# PCB_V1_7_1.net
KiCad netlist of a schematic drawn in EAGLE
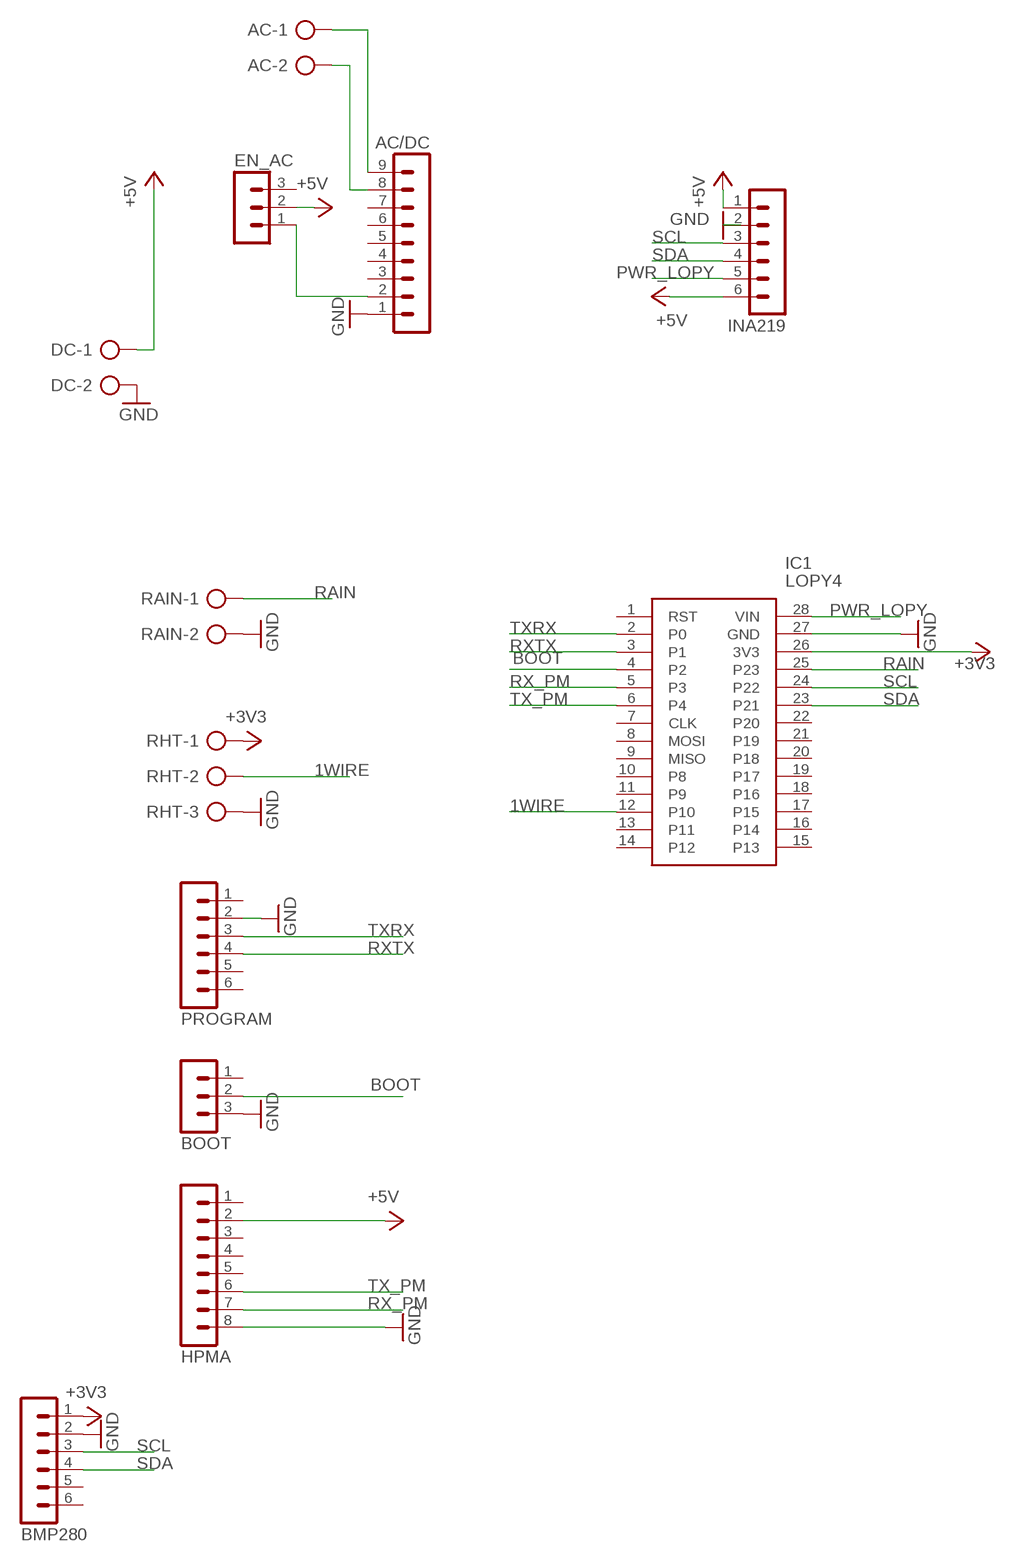
[diagram p0: schematic, sheet 1]

(export (version "E")
  (design (tool "Eeschema 10.0.6"))
  (components
    (comp (ref "AC")
      (value "AK300/2")
      (footprint "eagle-import:AK300_2")
      (libsource (lib "eagle-import") (part "AK300/2"))
    )
    (comp (ref "AC/DC")
      (value "MA09-1")
      (footprint "eagle-import:MA09-1")
      (libsource (lib "eagle-import") (part "MA09-1"))
    )
    (comp (ref "BMP280")
      (value "MA06-1")
      (footprint "eagle-import:MA06-1")
      (libsource (lib "eagle-import") (part "MA06-1"))
    )
    (comp (ref "BOOT")
      (value "MA03-1")
      (footprint "eagle-import:MA03-1")
      (libsource (lib "eagle-import") (part "MA03-1"))
    )
    (comp (ref "DC")
      (value "AK300/2")
      (footprint "eagle-import:AK300_2")
      (libsource (lib "eagle-import") (part "AK300/2"))
    )
    (comp (ref "EN_AC")
      (value "MA03-1")
      (footprint "eagle-import:MA03-1")
      (libsource (lib "eagle-import") (part "MA03-1"))
    )
    (comp (ref "HPMA")
      (value "MA08-1")
      (footprint "eagle-import:MA08-1")
      (libsource (lib "eagle-import") (part "MA08-1"))
    )
    (comp (ref "IC1")
      (value "LOPY4")
      (footprint "eagle-import:LOPY4")
      (fields (field (name "MOUSER_PART_NUMBER") "365-LOPY4"))
      (libsource (lib "eagle-import") (part "LOPY4"))
    )
    (comp (ref "INA219")
      (value "MA06-1")
      (footprint "eagle-import:MA06-1")
      (libsource (lib "eagle-import") (part "MA06-1"))
    )
    (comp (ref "PROGRAM")
      (value "MA06-1")
      (footprint "eagle-import:MA06-1")
      (libsource (lib "eagle-import") (part "MA06-1"))
    )
    (comp (ref "RAIN")
      (value "AK300/2")
      (footprint "eagle-import:AK300_2")
      (libsource (lib "eagle-import") (part "AK300/2"))
    )
    (comp (ref "RHT")
      (value "AK300/3")
      (footprint "eagle-import:AK300_3")
      (libsource (lib "eagle-import") (part "AK300/3"))
    )
  )
  (nets
    (net (code "1") (name "+3V3") (class "Default")
      (node (ref "BMP280") (pin "1") (pinfunction "1_1") (pintype "passive"))
      (node (ref "IC1") (pin "26") (pinfunction "3V3_26") (pintype "bidirectional"))
      (node (ref "RHT") (pin "1") (pinfunction "KL_1") (pintype "passive"))
    )
    (net (code "2") (name "+5V") (class "Default")
      (node (ref "DC") (pin "1") (pinfunction "KL_1") (pintype "passive"))
      (node (ref "EN_AC") (pin "2") (pinfunction "2_2") (pintype "passive"))
      (node (ref "HPMA") (pin "2") (pinfunction "2_2") (pintype "passive"))
      (node (ref "INA219") (pin "1") (pinfunction "1_1") (pintype "passive"))
      (node (ref "INA219") (pin "6") (pinfunction "6_6") (pintype "passive"))
    )
    (net (code "3") (name "/1WIRE") (class "Default")
      (node (ref "IC1") (pin "12") (pinfunction "P10_12") (pintype "bidirectional"))
      (node (ref "RHT") (pin "2") (pinfunction "KL_2") (pintype "passive"))
    )
    (net (code "4") (name "/BOOT") (class "Default")
      (node (ref "BOOT") (pin "2") (pinfunction "2_2") (pintype "passive"))
      (node (ref "IC1") (pin "4") (pinfunction "P2_4") (pintype "bidirectional"))
    )
    (net (code "5") (name "/PWR_LOPY") (class "Default")
      (node (ref "IC1") (pin "28") (pinfunction "VIN_28") (pintype "bidirectional"))
      (node (ref "INA219") (pin "5") (pinfunction "5_5") (pintype "passive"))
    )
    (net (code "6") (name "/RAIN") (class "Default")
      (node (ref "IC1") (pin "25") (pinfunction "P23_25") (pintype "bidirectional"))
      (node (ref "RAIN") (pin "1") (pinfunction "KL_1") (pintype "passive"))
    )
    (net (code "7") (name "/RXTX") (class "Default")
      (node (ref "IC1") (pin "3") (pinfunction "P1_3") (pintype "bidirectional"))
      (node (ref "PROGRAM") (pin "4") (pinfunction "4_4") (pintype "passive"))
    )
    (net (code "8") (name "/RX_PM") (class "Default")
      (node (ref "HPMA") (pin "7") (pinfunction "7_7") (pintype "passive"))
      (node (ref "IC1") (pin "5") (pinfunction "P3_5") (pintype "bidirectional"))
    )
    (net (code "9") (name "/SCL") (class "Default")
      (node (ref "BMP280") (pin "3") (pinfunction "3_3") (pintype "passive"))
      (node (ref "IC1") (pin "24") (pinfunction "P22_24") (pintype "bidirectional"))
      (node (ref "INA219") (pin "3") (pinfunction "3_3") (pintype "passive"))
    )
    (net (code "10") (name "/SDA") (class "Default")
      (node (ref "BMP280") (pin "4") (pinfunction "4_4") (pintype "passive"))
      (node (ref "IC1") (pin "23") (pinfunction "P21_23") (pintype "bidirectional"))
      (node (ref "INA219") (pin "4") (pinfunction "4_4") (pintype "passive"))
    )
    (net (code "11") (name "/TXRX") (class "Default")
      (node (ref "IC1") (pin "2") (pinfunction "P0_2") (pintype "bidirectional"))
      (node (ref "PROGRAM") (pin "3") (pinfunction "3_3") (pintype "passive"))
    )
    (net (code "12") (name "/TX_PM") (class "Default")
      (node (ref "HPMA") (pin "6") (pinfunction "6_6") (pintype "passive"))
      (node (ref "IC1") (pin "6") (pinfunction "P4_6") (pintype "bidirectional"))
    )
    (net (code "13") (name "GND") (class "Default")
      (node (ref "AC/DC") (pin "1") (pinfunction "1_1") (pintype "passive"))
      (node (ref "BMP280") (pin "2") (pinfunction "2_2") (pintype "passive"))
      (node (ref "BOOT") (pin "3") (pinfunction "3_3") (pintype "passive"))
      (node (ref "DC") (pin "2") (pinfunction "KL_2") (pintype "passive"))
      (node (ref "HPMA") (pin "8") (pinfunction "8_8") (pintype "passive"))
      (node (ref "IC1") (pin "27") (pinfunction "GND_27") (pintype "bidirectional"))
      (node (ref "INA219") (pin "2") (pinfunction "2_2") (pintype "passive"))
      (node (ref "PROGRAM") (pin "2") (pinfunction "2_2") (pintype "passive"))
      (node (ref "RAIN") (pin "2") (pinfunction "KL_2") (pintype "passive"))
      (node (ref "RHT") (pin "3") (pinfunction "KL_3") (pintype "passive"))
    )
    (net (code "14") (name "Net-(AC/DC-Pad2)") (class "Default")
      (node (ref "AC/DC") (pin "2") (pinfunction "2_2") (pintype "passive"))
      (node (ref "EN_AC") (pin "1") (pinfunction "1_1") (pintype "passive"))
    )
    (net (code "15") (name "Net-(ACA-KL)") (class "Default")
      (node (ref "AC") (pin "1") (pinfunction "KL_1") (pintype "passive"))
      (node (ref "AC/DC") (pin "9") (pinfunction "9_9") (pintype "passive"))
    )
    (net (code "16") (name "Net-(ACB-KL)") (class "Default")
      (node (ref "AC") (pin "2") (pinfunction "KL_2") (pintype "passive"))
      (node (ref "AC/DC") (pin "8") (pinfunction "8_8") (pintype "passive"))
    )
    (net (code "17") (name "unconnected-(AC/DC-Pad3)") (class "Default")
      (node (ref "AC/DC") (pin "3") (pinfunction "3_3") (pintype "passive"))
    )
    (net (code "18") (name "unconnected-(AC/DC-Pad4)") (class "Default")
      (node (ref "AC/DC") (pin "4") (pinfunction "4_4") (pintype "passive"))
    )
    (net (code "19") (name "unconnected-(AC/DC-Pad5)") (class "Default")
      (node (ref "AC/DC") (pin "5") (pinfunction "5_5") (pintype "passive"))
    )
    (net (code "20") (name "unconnected-(AC/DC-Pad6)") (class "Default")
      (node (ref "AC/DC") (pin "6") (pinfunction "6_6") (pintype "passive"))
    )
    (net (code "21") (name "unconnected-(AC/DC-Pad7)") (class "Default")
      (node (ref "AC/DC") (pin "7") (pinfunction "7_7") (pintype "passive"))
    )
    (net (code "22") (name "unconnected-(BMP280-Pad5)") (class "Default")
      (node (ref "BMP280") (pin "5") (pinfunction "5_5") (pintype "passive"))
    )
    (net (code "23") (name "unconnected-(BMP280-Pad6)") (class "Default")
      (node (ref "BMP280") (pin "6") (pinfunction "6_6") (pintype "passive"))
    )
    (net (code "24") (name "unconnected-(BOOT-Pad1)") (class "Default")
      (node (ref "BOOT") (pin "1") (pinfunction "1_1") (pintype "passive"))
    )
    (net (code "25") (name "unconnected-(EN_AC-Pad3)") (class "Default")
      (node (ref "EN_AC") (pin "3") (pinfunction "3_3") (pintype "passive"))
    )
    (net (code "26") (name "unconnected-(HPMA-Pad1)") (class "Default")
      (node (ref "HPMA") (pin "1") (pinfunction "1_1") (pintype "passive"))
    )
    (net (code "27") (name "unconnected-(HPMA-Pad3)") (class "Default")
      (node (ref "HPMA") (pin "3") (pinfunction "3_3") (pintype "passive"))
    )
    (net (code "28") (name "unconnected-(HPMA-Pad4)") (class "Default")
      (node (ref "HPMA") (pin "4") (pinfunction "4_4") (pintype "passive"))
    )
    (net (code "29") (name "unconnected-(HPMA-Pad5)") (class "Default")
      (node (ref "HPMA") (pin "5") (pinfunction "5_5") (pintype "passive"))
    )
    (net (code "30") (name "unconnected-(IC1-CLK-Pad7)") (class "Default")
      (node (ref "IC1") (pin "7") (pinfunction "CLK_7") (pintype "bidirectional"))
    )
    (net (code "31") (name "unconnected-(IC1-MISO-Pad9)") (class "Default")
      (node (ref "IC1") (pin "9") (pinfunction "MISO_9") (pintype "bidirectional"))
    )
    (net (code "32") (name "unconnected-(IC1-MOSI-Pad8)") (class "Default")
      (node (ref "IC1") (pin "8") (pinfunction "MOSI_8") (pintype "bidirectional"))
    )
    (net (code "33") (name "unconnected-(IC1-P8-Pad10)") (class "Default")
      (node (ref "IC1") (pin "10") (pinfunction "P8_10") (pintype "bidirectional"))
    )
    (net (code "34") (name "unconnected-(IC1-P9-Pad11)") (class "Default")
      (node (ref "IC1") (pin "11") (pinfunction "P9_11") (pintype "bidirectional"))
    )
    (net (code "35") (name "unconnected-(IC1-P11-Pad13)") (class "Default")
      (node (ref "IC1") (pin "13") (pinfunction "P11_13") (pintype "bidirectional"))
    )
    (net (code "36") (name "unconnected-(IC1-P12-Pad14)") (class "Default")
      (node (ref "IC1") (pin "14") (pinfunction "P12_14") (pintype "bidirectional"))
    )
    (net (code "37") (name "unconnected-(IC1-P13-Pad15)") (class "Default")
      (node (ref "IC1") (pin "15") (pinfunction "P13_15") (pintype "bidirectional"))
    )
    (net (code "38") (name "unconnected-(IC1-P14-Pad16)") (class "Default")
      (node (ref "IC1") (pin "16") (pinfunction "P14_16") (pintype "bidirectional"))
    )
    (net (code "39") (name "unconnected-(IC1-P15-Pad17)") (class "Default")
      (node (ref "IC1") (pin "17") (pinfunction "P15_17") (pintype "bidirectional"))
    )
    (net (code "40") (name "unconnected-(IC1-P16-Pad18)") (class "Default")
      (node (ref "IC1") (pin "18") (pinfunction "P16_18") (pintype "bidirectional"))
    )
    (net (code "41") (name "unconnected-(IC1-P17-Pad19)") (class "Default")
      (node (ref "IC1") (pin "19") (pinfunction "P17_19") (pintype "bidirectional"))
    )
    (net (code "42") (name "unconnected-(IC1-P18-Pad20)") (class "Default")
      (node (ref "IC1") (pin "20") (pinfunction "P18_20") (pintype "bidirectional"))
    )
    (net (code "43") (name "unconnected-(IC1-P19-Pad21)") (class "Default")
      (node (ref "IC1") (pin "21") (pinfunction "P19_21") (pintype "bidirectional"))
    )
    (net (code "44") (name "unconnected-(IC1-P20-Pad22)") (class "Default")
      (node (ref "IC1") (pin "22") (pinfunction "P20_22") (pintype "bidirectional"))
    )
    (net (code "45") (name "unconnected-(IC1-RST-Pad1)") (class "Default")
      (node (ref "IC1") (pin "1") (pinfunction "RST_1") (pintype "bidirectional"))
    )
    (net (code "46") (name "unconnected-(PROGRAM-Pad1)") (class "Default")
      (node (ref "PROGRAM") (pin "1") (pinfunction "1_1") (pintype "passive"))
    )
    (net (code "47") (name "unconnected-(PROGRAM-Pad5)") (class "Default")
      (node (ref "PROGRAM") (pin "5") (pinfunction "5_5") (pintype "passive"))
    )
    (net (code "48") (name "unconnected-(PROGRAM-Pad6)") (class "Default")
      (node (ref "PROGRAM") (pin "6") (pinfunction "6_6") (pintype "passive"))
    )
  )
)
